# SCH_Blink-Board_Easyeda.net
KiCad netlist of a schematic drawn in EasyEDA
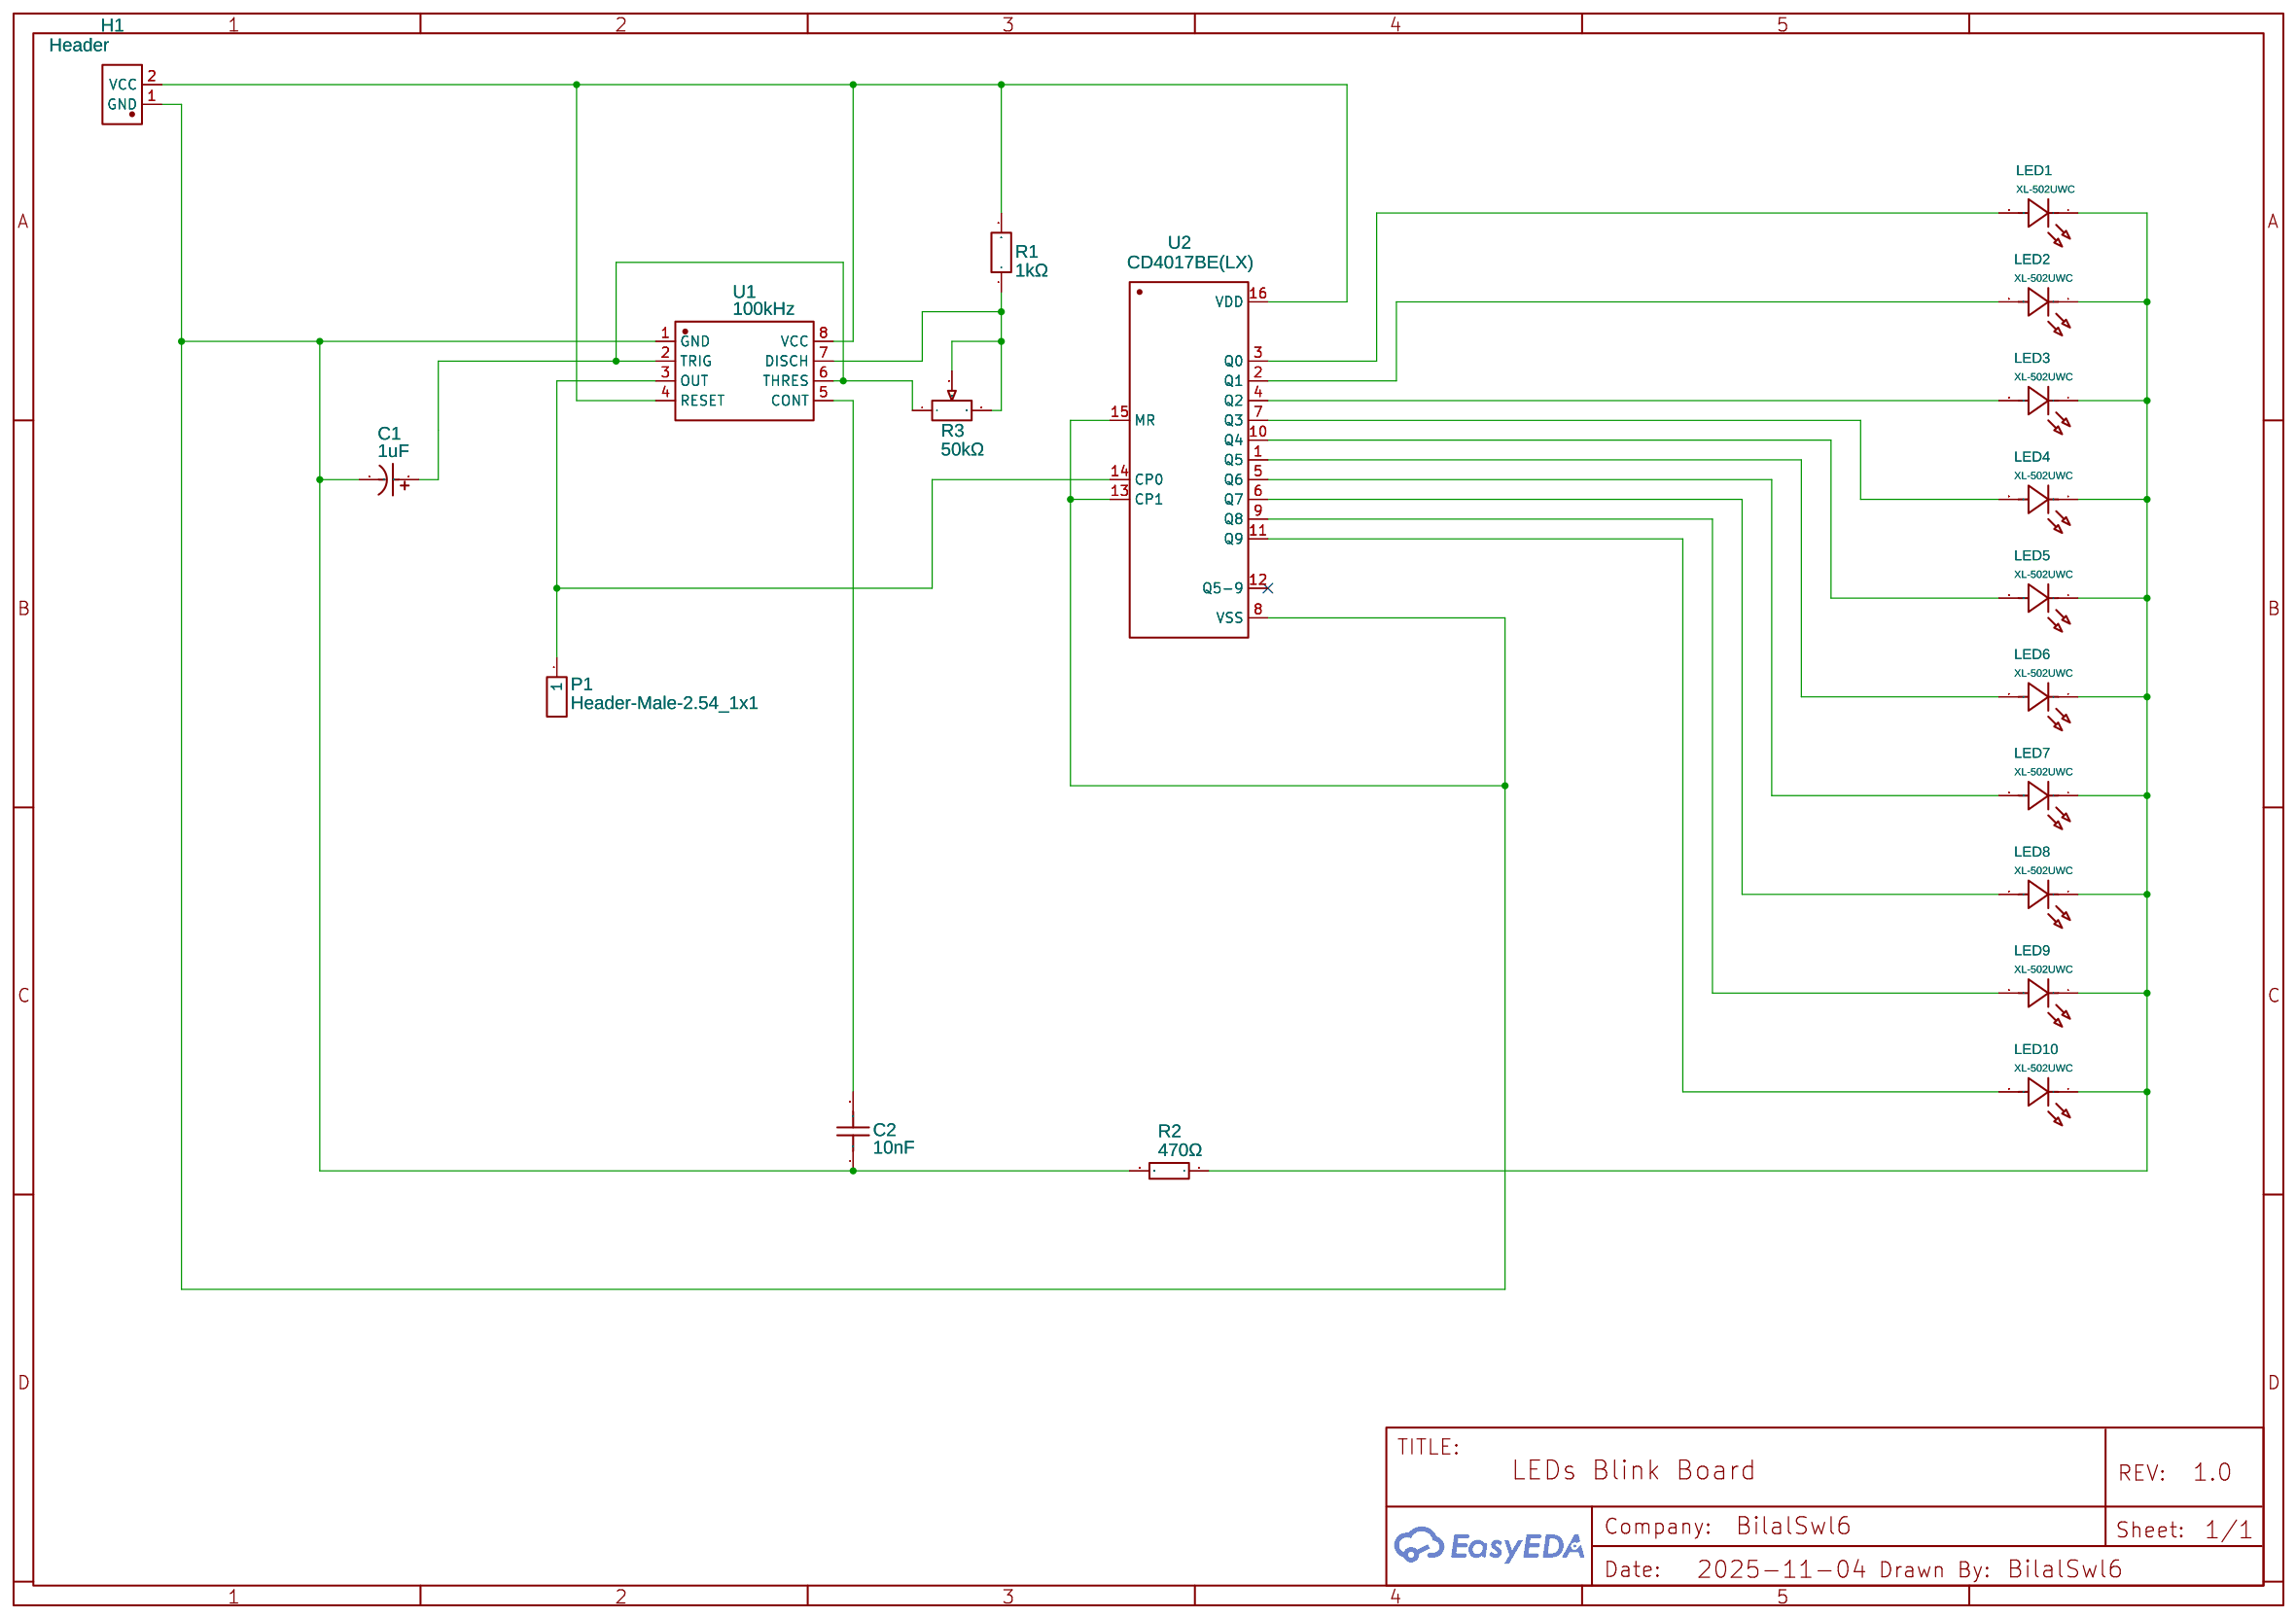
[diagram p0: schematic sheet]

(export (version "E")
  (design (tool "Eeschema 10.0.6"))
  (components
    (comp (ref "C1")
      (value "1uF")
      (fields (field (name "Manufacturer Part") "KF010M050C110A") (field (name "Manufacturer") "CapXon(丰宾)"))
      (libsource (lib "") (part "KF010M050C110A"))
    )
    (comp (ref "C2")
      (value "10nF")
      (fields (field (name "Manufacturer Part") "N09F1B103MN0B0S0N0") (field (name "Manufacturer") "STE(松田)"))
      (libsource (lib "") (part "N09F1B103MN0B0S0N0"))
    )
    (comp (ref "H1")
      (value "Header")
      (fields (field (name "Manufacturer Part") "PZ254V-11-02P") (field (name "Manufacturer") "XFCN(兴飞)"))
      (libsource (lib "") (part "PZ254V-11-02P"))
    )
    (comp (ref "LED1")
      (value "XL-502UWC")
      (fields (field (name "Manufacturer") "XINGLIGHT(成兴光)"))
      (libsource (lib "") (part "XL-502UWC"))
    )
    (comp (ref "LED2")
      (value "XL-502UWC")
      (fields (field (name "Manufacturer") "XINGLIGHT(成兴光)"))
      (libsource (lib "") (part "XL-502UWC"))
    )
    (comp (ref "LED3")
      (value "XL-502UWC")
      (fields (field (name "Manufacturer") "XINGLIGHT(成兴光)"))
      (libsource (lib "") (part "XL-502UWC"))
    )
    (comp (ref "LED4")
      (value "XL-502UWC")
      (fields (field (name "Manufacturer") "XINGLIGHT(成兴光)"))
      (libsource (lib "") (part "XL-502UWC"))
    )
    (comp (ref "LED5")
      (value "XL-502UWC")
      (fields (field (name "Manufacturer") "XINGLIGHT(成兴光)"))
      (libsource (lib "") (part "XL-502UWC"))
    )
    (comp (ref "LED6")
      (value "XL-502UWC")
      (fields (field (name "Manufacturer") "XINGLIGHT(成兴光)"))
      (libsource (lib "") (part "XL-502UWC"))
    )
    (comp (ref "LED7")
      (value "XL-502UWC")
      (fields (field (name "Manufacturer") "XINGLIGHT(成兴光)"))
      (libsource (lib "") (part "XL-502UWC"))
    )
    (comp (ref "LED8")
      (value "XL-502UWC")
      (fields (field (name "Manufacturer") "XINGLIGHT(成兴光)"))
      (libsource (lib "") (part "XL-502UWC"))
    )
    (comp (ref "LED9")
      (value "XL-502UWC")
      (fields (field (name "Manufacturer") "XINGLIGHT(成兴光)"))
      (libsource (lib "") (part "XL-502UWC"))
    )
    (comp (ref "LED10")
      (value "XL-502UWC")
      (fields (field (name "Manufacturer") "XINGLIGHT(成兴光)"))
      (libsource (lib "") (part "XL-502UWC"))
    )
    (comp (ref "P1")
      (value "Header-Male-2.54_1x1")
      (fields (field (name "Manufacturer Part") "2.54-1*1P针") (field (name "Manufacturer") "BOOMELE(博穆精密)"))
      (libsource (lib "") (part "Header-Male-2.54_1x1"))
    )
    (comp (ref "R1")
      (value "1kΩ")
      (fields (field (name "Manufacturer Part") "MF1/4W-1KΩ±1%T52") (field (name "Manufacturer") "华星机电"))
      (libsource (lib "") (part "MF1/4W-1KΩ±1%T52"))
    )
    (comp (ref "R2")
      (value "470Ω")
      (fields
        (field (name "Manufacturer Part") "MFR0W4F4700A50")
        (field (name "Manufacturer") "UNI-ROYAL(厚声)")
      )
      (libsource (lib "") (part "MFR0W4F4700A50"))
    )
    (comp (ref "R3")
      (value "50kΩ")
      (fields (field (name "Manufacturer Part") "3296X-1-503") (field (name "Manufacturer") "BOCHEN(博晨)"))
      (libsource (lib "") (part "3296X-1-503_C118912"))
    )
    (comp (ref "U1")
      (value "100kHz")
      (fields (field (name "Manufacturer Part") "NE555P") (field (name "Manufacturer") "TI(德州仪器)"))
      (libsource (lib "") (part "NE555P"))
    )
    (comp (ref "U2")
      (value "CD4017BE(LX)")
      (fields (field (name "Manufacturer") "LX(灵星芯微)"))
      (libsource (lib "") (part "CD4017BE(LX)"))
    )
  )
  (nets
    (net (code "1") (name "Net-(H1-GND)") (class "Default")
      (node (ref "C1") (pin "2") (pinfunction "2_2") (pintype "input"))
      (node (ref "C2") (pin "1") (pinfunction "1_1") (pintype "unspecified"))
      (node (ref "H1") (pin "1") (pinfunction "GND_1") (pintype "unspecified"))
      (node (ref "R2") (pin "2") (pinfunction "2_2") (pintype "input"))
      (node (ref "U1") (pin "1") (pinfunction "GND_1") (pintype "unspecified"))
      (node (ref "U2") (pin "13") (pinfunction "CP1_13") (pintype "unspecified"))
      (node (ref "U2") (pin "15") (pinfunction "MR_15") (pintype "unspecified"))
      (node (ref "U2") (pin "8") (pinfunction "VSS_8") (pintype "unspecified"))
    )
    (net (code "2") (name "Net-(H1-VCC)") (class "Default")
      (node (ref "H1") (pin "2") (pinfunction "VCC_2") (pintype "unspecified"))
      (node (ref "R1") (pin "2") (pinfunction "2_2") (pintype "unspecified"))
      (node (ref "U1") (pin "4") (pinfunction "RESET_4") (pintype "unspecified"))
      (node (ref "U1") (pin "8") (pinfunction "VCC_8") (pintype "unspecified"))
      (node (ref "U2") (pin "16") (pinfunction "VDD_16") (pintype "unspecified"))
    )
    (net (code "3") (name "Net-(LED1-A)") (class "Default")
      (node (ref "LED1") (pin "2") (pinfunction "A_2") (pintype "unspecified"))
      (node (ref "U2") (pin "3") (pinfunction "Q0_3") (pintype "unspecified"))
    )
    (net (code "4") (name "Net-(LED1-K)") (class "Default")
      (node (ref "LED1") (pin "1") (pinfunction "K_1") (pintype "unspecified"))
      (node (ref "LED10") (pin "1") (pinfunction "K_1") (pintype "unspecified"))
      (node (ref "LED2") (pin "1") (pinfunction "K_1") (pintype "unspecified"))
      (node (ref "LED3") (pin "1") (pinfunction "K_1") (pintype "unspecified"))
      (node (ref "LED4") (pin "1") (pinfunction "K_1") (pintype "unspecified"))
      (node (ref "LED5") (pin "1") (pinfunction "K_1") (pintype "unspecified"))
      (node (ref "LED6") (pin "1") (pinfunction "K_1") (pintype "unspecified"))
      (node (ref "LED7") (pin "1") (pinfunction "K_1") (pintype "unspecified"))
      (node (ref "LED8") (pin "1") (pinfunction "K_1") (pintype "unspecified"))
      (node (ref "LED9") (pin "1") (pinfunction "K_1") (pintype "unspecified"))
      (node (ref "R2") (pin "1") (pinfunction "1_1") (pintype "input"))
    )
    (net (code "5") (name "Net-(LED2-A)") (class "Default")
      (node (ref "LED2") (pin "2") (pinfunction "A_2") (pintype "unspecified"))
      (node (ref "U2") (pin "2") (pinfunction "Q1_2") (pintype "unspecified"))
    )
    (net (code "6") (name "Net-(LED3-A)") (class "Default")
      (node (ref "LED3") (pin "2") (pinfunction "A_2") (pintype "unspecified"))
      (node (ref "U2") (pin "4") (pinfunction "Q2_4") (pintype "unspecified"))
    )
    (net (code "7") (name "Net-(LED4-A)") (class "Default")
      (node (ref "LED4") (pin "2") (pinfunction "A_2") (pintype "unspecified"))
      (node (ref "U2") (pin "7") (pinfunction "Q3_7") (pintype "unspecified"))
    )
    (net (code "8") (name "Net-(LED5-A)") (class "Default")
      (node (ref "LED5") (pin "2") (pinfunction "A_2") (pintype "unspecified"))
      (node (ref "U2") (pin "10") (pinfunction "Q4_10") (pintype "unspecified"))
    )
    (net (code "9") (name "Net-(LED6-A)") (class "Default")
      (node (ref "LED6") (pin "2") (pinfunction "A_2") (pintype "unspecified"))
      (node (ref "U2") (pin "1") (pinfunction "Q5_1") (pintype "unspecified"))
    )
    (net (code "10") (name "Net-(LED7-A)") (class "Default")
      (node (ref "LED7") (pin "2") (pinfunction "A_2") (pintype "unspecified"))
      (node (ref "U2") (pin "5") (pinfunction "Q6_5") (pintype "unspecified"))
    )
    (net (code "11") (name "Net-(LED8-A)") (class "Default")
      (node (ref "LED8") (pin "2") (pinfunction "A_2") (pintype "unspecified"))
      (node (ref "U2") (pin "6") (pinfunction "Q7_6") (pintype "unspecified"))
    )
    (net (code "12") (name "Net-(LED9-A)") (class "Default")
      (node (ref "LED9") (pin "2") (pinfunction "A_2") (pintype "unspecified"))
      (node (ref "U2") (pin "9") (pinfunction "Q8_9") (pintype "unspecified"))
    )
    (net (code "13") (name "Net-(LED10-A)") (class "Default")
      (node (ref "LED10") (pin "2") (pinfunction "A_2") (pintype "unspecified"))
      (node (ref "U2") (pin "11") (pinfunction "Q9_11") (pintype "unspecified"))
    )
    (net (code "14") (name "Net-(U1-CONT)") (class "Default")
      (node (ref "C2") (pin "2") (pinfunction "2_2") (pintype "unspecified"))
      (node (ref "U1") (pin "5") (pinfunction "CONT_5") (pintype "unspecified"))
    )
    (net (code "15") (name "Net-(U1-DISCH)") (class "Default")
      (node (ref "R1") (pin "1") (pinfunction "1_1") (pintype "unspecified"))
      (node (ref "R3") (pin "2") (pinfunction "2_2") (pintype "input"))
      (node (ref "R3") (pin "3") (pinfunction "3_3") (pintype "input"))
      (node (ref "U1") (pin "7") (pinfunction "DISCH_7") (pintype "unspecified"))
    )
    (net (code "16") (name "Net-(U1-OUT)") (class "Default")
      (node (ref "P1") (pin "1") (pinfunction "1_1") (pintype "input"))
      (node (ref "U1") (pin "3") (pinfunction "OUT_3") (pintype "unspecified"))
      (node (ref "U2") (pin "14") (pinfunction "CP0_14") (pintype "unspecified"))
    )
    (net (code "17") (name "Net-(U1-THRES)") (class "Default")
      (node (ref "C1") (pin "1") (pinfunction "1_1") (pintype "input"))
      (node (ref "R3") (pin "1") (pinfunction "1_1") (pintype "input"))
      (node (ref "U1") (pin "2") (pinfunction "TRIG_2") (pintype "unspecified"))
      (node (ref "U1") (pin "6") (pinfunction "THRES_6") (pintype "unspecified"))
    )
    (net (code "18") (name "unconnected-(U2-Q5-9-Pad12)") (class "Default")
      (node (ref "U2") (pin "12") (pinfunction "Q5-9_12") (pintype "unspecified+no_connect"))
    )
  )
)
